# avr.net
KiCad netlist of a schematic drawn in EAGLE
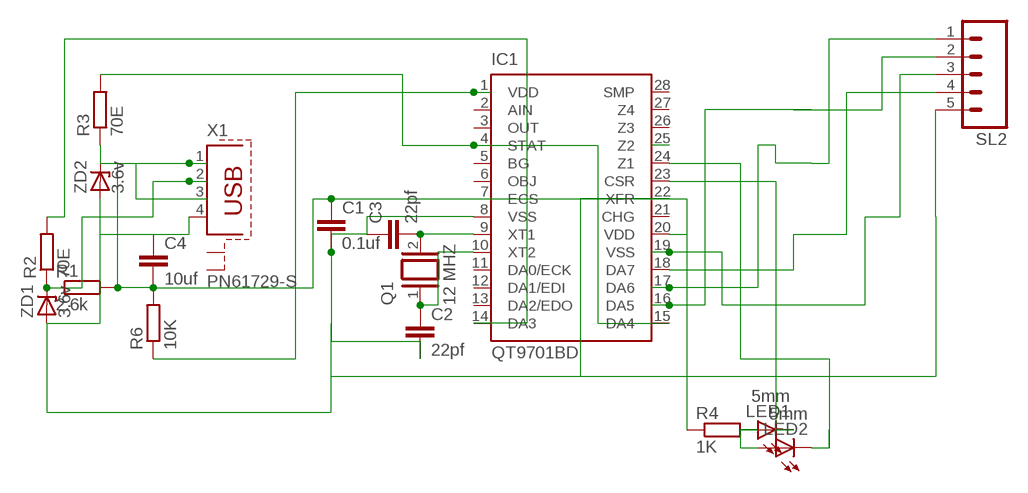
[diagram p0: schematic, sheet 1]

(export (version "E")
  (design (tool "Eeschema 10.0.6"))
  (components
    (comp (ref "C1")
      (value "0.1uf")
      (footprint "eagle-import:C2.5-3")
      (libsource (lib "eagle-import") (part "C2,5-3"))
    )
    (comp (ref "C2")
      (value "22pf")
      (footprint "eagle-import:C2.5-3")
      (libsource (lib "eagle-import") (part "C2,5-3"))
    )
    (comp (ref "C3")
      (value "22pf")
      (footprint "eagle-import:C2.5-3")
      (libsource (lib "eagle-import") (part "C2,5-3"))
    )
    (comp (ref "C4")
      (value "10uf")
      (footprint "eagle-import:C2.5-3")
      (libsource (lib "eagle-import") (part "C2,5-3"))
    )
    (comp (ref "IC1")
      (value "QT9701BD")
      (footprint "eagle-import:DIL28-3")
      (libsource (lib "eagle-import") (part "QT9701BD"))
    )
    (comp (ref "LED1")
      (value "5mm")
      (footprint "eagle-import:LED3MM")
      (libsource (lib "eagle-import") (part "LED3MM"))
    )
    (comp (ref "LED2")
      (value "5mm")
      (footprint "eagle-import:LED3MM")
      (libsource (lib "eagle-import") (part "LED3MM"))
    )
    (comp (ref "Q1")
      (value "12 MHZ")
      (footprint "eagle-import:QS")
      (libsource (lib "eagle-import") (part "XTAL/S"))
    )
    (comp (ref "R1")
      (value "2.6k")
      (footprint "eagle-import:0204_7")
      (libsource (lib "eagle-import") (part "R-EU_0204/7"))
    )
    (comp (ref "R2")
      (value "70E")
      (footprint "eagle-import:0204_7")
      (libsource (lib "eagle-import") (part "R-EU_0204/7"))
    )
    (comp (ref "R3")
      (value "70E")
      (footprint "eagle-import:0204_7")
      (libsource (lib "eagle-import") (part "R-EU_0204/7"))
    )
    (comp (ref "R4")
      (value "1K")
      (footprint "eagle-import:0204_7")
      (libsource (lib "eagle-import") (part "R-EU_0204/7"))
    )
    (comp (ref "R6")
      (value "10K")
      (footprint "eagle-import:0204_7")
      (libsource (lib "eagle-import") (part "R-EU_0204/7"))
    )
    (comp (ref "SL2")
      (value "M05")
      (footprint "eagle-import:05P")
      (libsource (lib "eagle-import") (part "M05"))
    )
    (comp (ref "X1")
      (value "PN61729-S")
      (footprint "eagle-import:PN61729-S")
      (libsource (lib "eagle-import") (part "PN61729-S"))
    )
    (comp (ref "ZD1")
      (value "3.6v")
      (footprint "eagle-import:SOD81")
      (libsource (lib "eagle-import") (part "BZD23"))
    )
    (comp (ref "ZD2")
      (value "3.6v")
      (footprint "eagle-import:SOD81")
      (libsource (lib "eagle-import") (part "BZD23"))
    )
  )
  (nets
    (net (code "1") (name "Net-(IC1-CSR)") (class "Default")
      (node (ref "IC1") (pin "23") (pinfunction "CSR_23") (pintype "output"))
      (node (ref "LED1") (pin "K") (pinfunction "C_K") (pintype "passive"))
    )
    (net (code "2") (name "Net-(IC1-DA3)") (class "Default")
      (node (ref "IC1") (pin "14") (pinfunction "DA3_14") (pintype "output"))
      (node (ref "R2") (pin "2") (pinfunction "2_2") (pintype "passive"))
    )
    (net (code "3") (name "Net-(IC1-DA4)") (class "Default")
      (node (ref "IC1") (pin "15") (pinfunction "DA4_15") (pintype "output"))
      (node (ref "IC1") (pin "4") (pinfunction "STAT_4") (pintype "output"))
      (node (ref "R3") (pin "2") (pinfunction "2_2") (pintype "passive"))
    )
    (net (code "4") (name "Net-(IC1-DA5)") (class "Default")
      (node (ref "IC1") (pin "16") (pinfunction "DA5_16") (pintype "output"))
      (node (ref "SL2") (pin "2") (pinfunction "2_2") (pintype "passive"))
    )
    (net (code "5") (name "Net-(IC1-DA6)") (class "Default")
      (node (ref "IC1") (pin "17") (pinfunction "DA6_17") (pintype "output"))
      (node (ref "SL2") (pin "1") (pinfunction "1_1") (pintype "passive"))
    )
    (net (code "6") (name "Net-(IC1-DA7)") (class "Default")
      (node (ref "IC1") (pin "18") (pinfunction "DA7_18") (pintype "output"))
      (node (ref "SL2") (pin "4") (pinfunction "4_4") (pintype "passive"))
    )
    (net (code "7") (name "Net-(IC1-ECS)") (class "Default")
      (node (ref "C1") (pin "1") (pinfunction "1_1") (pintype "passive"))
      (node (ref "C4") (pin "2") (pinfunction "2_2") (pintype "passive"))
      (node (ref "IC1") (pin "20") (pinfunction "VDD_20") (pintype "input"))
      (node (ref "IC1") (pin "7") (pinfunction "ECS_7") (pintype "output"))
      (node (ref "R1") (pin "2") (pinfunction "2_2") (pintype "passive"))
      (node (ref "R4") (pin "1") (pinfunction "1_1") (pintype "passive"))
      (node (ref "R6") (pin "2") (pinfunction "2_2") (pintype "passive"))
      (node (ref "X1") (pin "1") (pinfunction "1_1") (pintype "passive"))
    )
    (net (code "8") (name "Net-(IC1-VDD-Pad1)") (class "Default")
      (node (ref "IC1") (pin "1") (pinfunction "VDD_1") (pintype "input"))
      (node (ref "R6") (pin "1") (pinfunction "1_1") (pintype "passive"))
    )
    (net (code "9") (name "Net-(IC1-VSS-Pad19)") (class "Default")
      (node (ref "IC1") (pin "19") (pinfunction "VSS_19") (pintype "input"))
      (node (ref "SL2") (pin "3") (pinfunction "3_3") (pintype "passive"))
    )
    (net (code "10") (name "Net-(IC1-XFR)") (class "Default")
      (node (ref "C1") (pin "2") (pinfunction "2_2") (pintype "passive"))
      (node (ref "C2") (pin "2") (pinfunction "2_2") (pintype "passive"))
      (node (ref "C3") (pin "1") (pinfunction "1_1") (pintype "passive"))
      (node (ref "C4") (pin "1") (pinfunction "1_1") (pintype "passive"))
      (node (ref "IC1") (pin "22") (pinfunction "XFR_22") (pintype "output"))
      (node (ref "IC1") (pin "8") (pinfunction "VSS_8") (pintype "input"))
      (node (ref "SL2") (pin "5") (pinfunction "5_5") (pintype "passive"))
      (node (ref "X1") (pin "4") (pinfunction "4_4") (pintype "passive"))
      (node (ref "ZD1") (pin "A") (pinfunction "A_A") (pintype "passive"))
      (node (ref "ZD2") (pin "A") (pinfunction "A_A") (pintype "passive"))
    )
    (net (code "11") (name "Net-(IC1-XT1)") (class "Default")
      (node (ref "C3") (pin "2") (pinfunction "2_2") (pintype "passive"))
      (node (ref "IC1") (pin "9") (pinfunction "XT1_9") (pintype "input"))
      (node (ref "Q1") (pin "2") (pinfunction "2_2") (pintype "passive"))
    )
    (net (code "12") (name "Net-(IC1-XT2)") (class "Default")
      (node (ref "C2") (pin "1") (pinfunction "1_1") (pintype "passive"))
      (node (ref "IC1") (pin "10") (pinfunction "XT2_10") (pintype "output"))
      (node (ref "Q1") (pin "1") (pinfunction "1_1") (pintype "passive"))
    )
    (net (code "13") (name "Net-(IC1-Z1)") (class "Default")
      (node (ref "IC1") (pin "24") (pinfunction "Z1_24") (pintype "output"))
      (node (ref "LED2") (pin "K") (pinfunction "C_K") (pintype "passive"))
    )
    (net (code "14") (name "Net-(LED1-PadA)") (class "Default")
      (node (ref "LED1") (pin "A") (pinfunction "A_A") (pintype "passive"))
      (node (ref "LED2") (pin "A") (pinfunction "A_A") (pintype "passive"))
      (node (ref "R4") (pin "2") (pinfunction "2_2") (pintype "passive"))
    )
    (net (code "15") (name "Net-(R1-Pad1)") (class "Default")
      (node (ref "R1") (pin "1") (pinfunction "1_1") (pintype "passive"))
      (node (ref "R2") (pin "1") (pinfunction "1_1") (pintype "passive"))
      (node (ref "X1") (pin "2") (pinfunction "2_2") (pintype "passive"))
      (node (ref "ZD1") (pin "C") (pinfunction "C_C") (pintype "passive"))
    )
    (net (code "16") (name "Net-(R3-Pad1)") (class "Default")
      (node (ref "R3") (pin "1") (pinfunction "1_1") (pintype "passive"))
      (node (ref "X1") (pin "3") (pinfunction "3_3") (pintype "passive"))
      (node (ref "ZD2") (pin "C") (pinfunction "C_C") (pintype "passive"))
    )
    (net (code "17") (name "unconnected-(IC1-AIN-Pad2)") (class "Default")
      (node (ref "IC1") (pin "2") (pinfunction "AIN_2") (pintype "input"))
    )
    (net (code "18") (name "unconnected-(IC1-BG-Pad5)") (class "Default")
      (node (ref "IC1") (pin "5") (pinfunction "BG_5") (pintype "input"))
    )
    (net (code "19") (name "unconnected-(IC1-CHG-Pad21)") (class "Default")
      (node (ref "IC1") (pin "21") (pinfunction "CHG_21") (pintype "output"))
    )
    (net (code "20") (name "unconnected-(IC1-DA0{slash}ECK-Pad11)") (class "Default")
      (node (ref "IC1") (pin "11") (pinfunction "DA0/ECK_11") (pintype "output"))
    )
    (net (code "21") (name "unconnected-(IC1-DA1{slash}EDI-Pad12)") (class "Default")
      (node (ref "IC1") (pin "12") (pinfunction "DA1/EDI_12") (pintype "output"))
    )
    (net (code "22") (name "unconnected-(IC1-DA2{slash}EDO-Pad13)") (class "Default")
      (node (ref "IC1") (pin "13") (pinfunction "DA2/EDO_13") (pintype "output"))
    )
    (net (code "23") (name "unconnected-(IC1-OBJ-Pad6)") (class "Default")
      (node (ref "IC1") (pin "6") (pinfunction "OBJ_6") (pintype "input"))
    )
    (net (code "24") (name "unconnected-(IC1-OUT-Pad3)") (class "Default")
      (node (ref "IC1") (pin "3") (pinfunction "OUT_3") (pintype "output"))
    )
    (net (code "25") (name "unconnected-(IC1-SMP-Pad28)") (class "Default")
      (node (ref "IC1") (pin "28") (pinfunction "SMP_28") (pintype "output"))
    )
    (net (code "26") (name "unconnected-(IC1-Z2-Pad25)") (class "Default")
      (node (ref "IC1") (pin "25") (pinfunction "Z2_25") (pintype "output"))
    )
    (net (code "27") (name "unconnected-(IC1-Z3-Pad26)") (class "Default")
      (node (ref "IC1") (pin "26") (pinfunction "Z3_26") (pintype "output"))
    )
    (net (code "28") (name "unconnected-(IC1-Z4-Pad27)") (class "Default")
      (node (ref "IC1") (pin "27") (pinfunction "Z4_27") (pintype "output"))
    )
    (net (code "29") (name "unconnected-(X1-PadS1)") (class "Default")
      (node (ref "X1") (pin "S1") (pinfunction "S1_S1") (pintype "passive"))
    )
    (net (code "30") (name "unconnected-(X1-PadS2)") (class "Default")
      (node (ref "X1") (pin "S2") (pinfunction "S2_S2") (pintype "passive"))
    )
  )
)
